# ProProject__CW32__2024-01-01.net
KiCad netlist of a schematic drawn in EasyEDA Pro
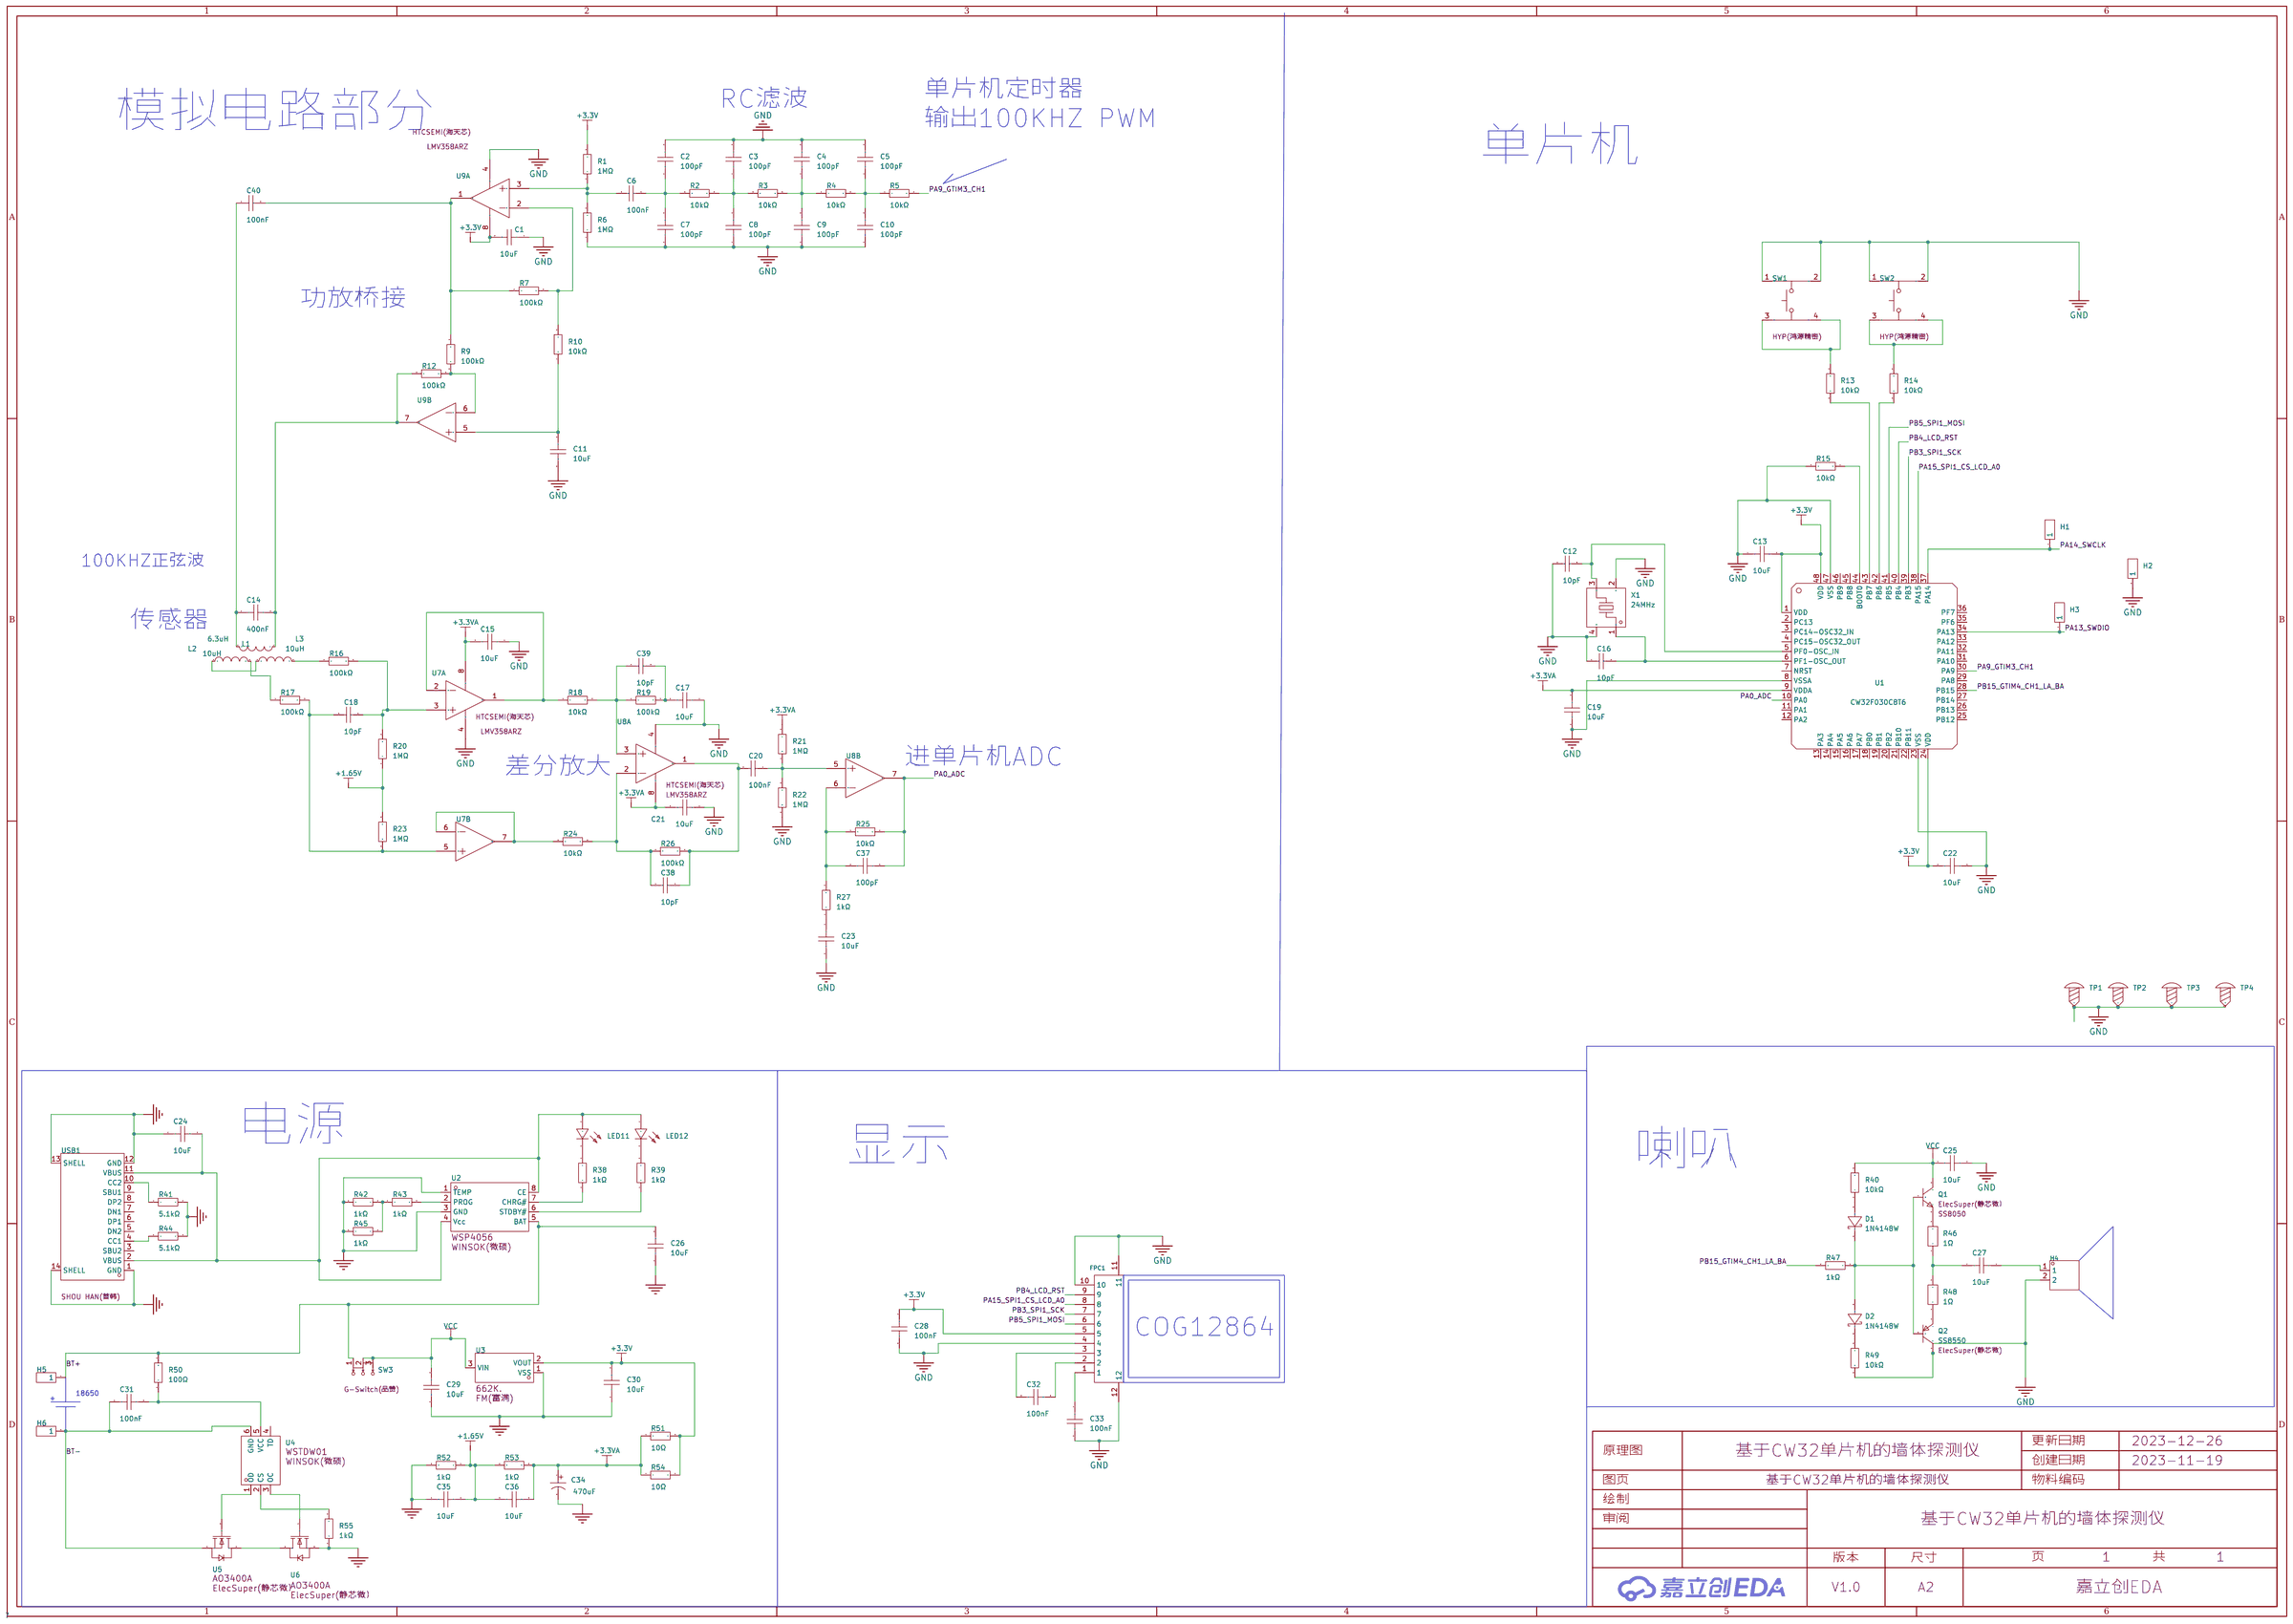
[diagram p0: schematic sheet]

(export (version "E")
  (design (tool "Eeschema 10.0.6"))
  (components
    (comp (ref "C1")
      (value "10uF")
      (footprint "easyedapro:C0603")
      (description "容值:10uF;精度:±10%;额定电压:10V;材质(温度系数):X5R;")
      (fields
        (field (name "Manufacturer Part") "CL10A106KP8NNNC")
        (field (name "Manufacturer") "SAMSUNG(三星)")
      )
      (libsource (lib "easyedapro") (part "CL10A106KP8NNNC"))
    )
    (comp (ref "C2")
      (value "100pF")
      (footprint "easyedapro:C0603")
      (description "容值:100pF;精度:±5%;额定电压:50V;材质(温度系数):NP0;")
      (fields
        (field (name "Manufacturer Part") "CC0603JRNPO9BN101")
        (field (name "Manufacturer") "YAGEO(国巨)")
      )
      (libsource (lib "easyedapro") (part "CC0603JRNPO9BN101"))
    )
    (comp (ref "C3")
      (value "100pF")
      (footprint "easyedapro:C0603")
      (description "容值:100pF;精度:±5%;额定电压:50V;材质(温度系数):NP0;")
      (fields
        (field (name "Manufacturer Part") "CC0603JRNPO9BN101")
        (field (name "Manufacturer") "YAGEO(国巨)")
      )
      (libsource (lib "easyedapro") (part "CC0603JRNPO9BN101"))
    )
    (comp (ref "C4")
      (value "100pF")
      (footprint "easyedapro:C0603")
      (description "容值:100pF;精度:±5%;额定电压:50V;材质(温度系数):NP0;")
      (fields
        (field (name "Manufacturer Part") "CC0603JRNPO9BN101")
        (field (name "Manufacturer") "YAGEO(国巨)")
      )
      (libsource (lib "easyedapro") (part "CC0603JRNPO9BN101"))
    )
    (comp (ref "C5")
      (value "100pF")
      (footprint "easyedapro:C0603")
      (description "容值:100pF;精度:±5%;额定电压:50V;材质(温度系数):NP0;")
      (fields
        (field (name "Manufacturer Part") "CC0603JRNPO9BN101")
        (field (name "Manufacturer") "YAGEO(国巨)")
      )
      (libsource (lib "easyedapro") (part "CC0603JRNPO9BN101"))
    )
    (comp (ref "C6")
      (value "100nF")
      (footprint "easyedapro:C0603")
      (description "容值:100nF;精度:±10%;额定电压:50V;材质(温度系数):X7R;")
      (fields (field (name "Manufacturer Part") "0603B104K500NT") (field (name "Manufacturer") "FH(风华)"))
      (libsource (lib "easyedapro") (part "0603B104K500NT"))
    )
    (comp (ref "C7")
      (value "100pF")
      (footprint "easyedapro:C0603")
      (description "容值:100pF;精度:±5%;额定电压:50V;材质(温度系数):NP0;")
      (fields
        (field (name "Manufacturer Part") "CC0603JRNPO9BN101")
        (field (name "Manufacturer") "YAGEO(国巨)")
      )
      (libsource (lib "easyedapro") (part "CC0603JRNPO9BN101"))
    )
    (comp (ref "C8")
      (value "100pF")
      (footprint "easyedapro:C0603")
      (description "容值:100pF;精度:±5%;额定电压:50V;材质(温度系数):NP0;")
      (fields
        (field (name "Manufacturer Part") "CC0603JRNPO9BN101")
        (field (name "Manufacturer") "YAGEO(国巨)")
      )
      (libsource (lib "easyedapro") (part "CC0603JRNPO9BN101"))
    )
    (comp (ref "C9")
      (value "100pF")
      (footprint "easyedapro:C0603")
      (description "容值:100pF;精度:±5%;额定电压:50V;材质(温度系数):NP0;")
      (fields
        (field (name "Manufacturer Part") "CC0603JRNPO9BN101")
        (field (name "Manufacturer") "YAGEO(国巨)")
      )
      (libsource (lib "easyedapro") (part "CC0603JRNPO9BN101"))
    )
    (comp (ref "C10")
      (value "100pF")
      (footprint "easyedapro:C0603")
      (description "容值:100pF;精度:±5%;额定电压:50V;材质(温度系数):NP0;")
      (fields
        (field (name "Manufacturer Part") "CC0603JRNPO9BN101")
        (field (name "Manufacturer") "YAGEO(国巨)")
      )
      (libsource (lib "easyedapro") (part "CC0603JRNPO9BN101"))
    )
    (comp (ref "C11")
      (value "10uF")
      (footprint "easyedapro:C0603")
      (description "容值:10uF;精度:±10%;额定电压:10V;材质(温度系数):X5R;")
      (fields
        (field (name "Manufacturer Part") "CL10A106KP8NNNC")
        (field (name "Manufacturer") "SAMSUNG(三星)")
      )
      (libsource (lib "easyedapro") (part "CL10A106KP8NNNC"))
    )
    (comp (ref "C12")
      (value "10pF")
      (footprint "easyedapro:C0603")
      (description "容值:10pF;精度:±5%;额定电压:50V;材质(温度系数):NP0;")
      (fields
        (field (name "Manufacturer Part") "CC0603JRNPO9BN100")
        (field (name "Manufacturer") "YAGEO(国巨)")
      )
      (libsource (lib "easyedapro") (part "CC0603JRNPO9BN100"))
    )
    (comp (ref "C13")
      (value "10uF")
      (footprint "easyedapro:C0603")
      (description "容值:10uF;精度:±10%;额定电压:10V;材质(温度系数):X5R;")
      (fields
        (field (name "Manufacturer Part") "CL10A106KP8NNNC")
        (field (name "Manufacturer") "SAMSUNG(三星)")
      )
      (libsource (lib "easyedapro") (part "CL10A106KP8NNNC"))
    )
    (comp (ref "C14")
      (value "400nF")
      (footprint "easyedapro:CAP-TH_L10.5-W6.0-P7.50-D1.2")
      (description "容值:400nF;精度:±5%;额定电压:100V;")
      (fields (field (name "Manufacturer Part") "MPP404J2A0701") (field (name "Manufacturer") "KYET(科雅)"))
      (libsource (lib "easyedapro") (part "MPP404J2A0701"))
    )
    (comp (ref "C15")
      (value "10uF")
      (footprint "easyedapro:C0603")
      (description "容值:10uF;精度:±10%;额定电压:10V;材质(温度系数):X5R;")
      (fields
        (field (name "Manufacturer Part") "CL10A106KP8NNNC")
        (field (name "Manufacturer") "SAMSUNG(三星)")
      )
      (libsource (lib "easyedapro") (part "CL10A106KP8NNNC"))
    )
    (comp (ref "C16")
      (value "10pF")
      (footprint "easyedapro:C0603")
      (description "容值:10pF;精度:±5%;额定电压:50V;材质(温度系数):NP0;")
      (fields
        (field (name "Manufacturer Part") "CC0603JRNPO9BN100")
        (field (name "Manufacturer") "YAGEO(国巨)")
      )
      (libsource (lib "easyedapro") (part "CC0603JRNPO9BN100"))
    )
    (comp (ref "C17")
      (value "10uF")
      (footprint "easyedapro:C0603")
      (description "容值:10uF;精度:±10%;额定电压:10V;材质(温度系数):X5R;")
      (fields
        (field (name "Manufacturer Part") "CL10A106KP8NNNC")
        (field (name "Manufacturer") "SAMSUNG(三星)")
      )
      (libsource (lib "easyedapro") (part "CL10A106KP8NNNC"))
    )
    (comp (ref "C18")
      (value "10pF")
      (footprint "easyedapro:C0603")
      (description "容值:10pF;精度:±5%;额定电压:50V;材质(温度系数):NP0;")
      (fields
        (field (name "Manufacturer Part") "CC0603JRNPO9BN100")
        (field (name "Manufacturer") "YAGEO(国巨)")
      )
      (libsource (lib "easyedapro") (part "CC0603JRNPO9BN100"))
    )
    (comp (ref "C19")
      (value "10uF")
      (footprint "easyedapro:C0603")
      (description "容值:10uF;精度:±10%;额定电压:10V;材质(温度系数):X5R;")
      (fields
        (field (name "Manufacturer Part") "CL10A106KP8NNNC")
        (field (name "Manufacturer") "SAMSUNG(三星)")
      )
      (libsource (lib "easyedapro") (part "CL10A106KP8NNNC"))
    )
    (comp (ref "C20")
      (value "100nF")
      (footprint "easyedapro:C0603")
      (description "容值:100nF;精度:±10%;额定电压:50V;材质(温度系数):X7R;")
      (fields (field (name "Manufacturer Part") "0603B104K500NT") (field (name "Manufacturer") "FH(风华)"))
      (libsource (lib "easyedapro") (part "0603B104K500NT"))
    )
    (comp (ref "C21")
      (value "10uF")
      (footprint "easyedapro:C0603")
      (description "容值:10uF;精度:±10%;额定电压:10V;材质(温度系数):X5R;")
      (fields
        (field (name "Manufacturer Part") "CL10A106KP8NNNC")
        (field (name "Manufacturer") "SAMSUNG(三星)")
      )
      (libsource (lib "easyedapro") (part "CL10A106KP8NNNC"))
    )
    (comp (ref "C22")
      (value "10uF")
      (footprint "easyedapro:C0603")
      (description "容值:10uF;精度:±10%;额定电压:10V;材质(温度系数):X5R;")
      (fields
        (field (name "Manufacturer Part") "CL10A106KP8NNNC")
        (field (name "Manufacturer") "SAMSUNG(三星)")
      )
      (libsource (lib "easyedapro") (part "CL10A106KP8NNNC"))
    )
    (comp (ref "C23")
      (value "10uF")
      (footprint "easyedapro:C0603")
      (description "容值:10uF;精度:±10%;额定电压:10V;材质(温度系数):X5R;")
      (fields
        (field (name "Manufacturer Part") "CL10A106KP8NNNC")
        (field (name "Manufacturer") "SAMSUNG(三星)")
      )
      (libsource (lib "easyedapro") (part "CL10A106KP8NNNC"))
    )
    (comp (ref "C24")
      (value "10uF")
      (footprint "easyedapro:C0603")
      (description "容值:10uF;精度:±10%;额定电压:10V;材质(温度系数):X5R;")
      (fields
        (field (name "Manufacturer Part") "CL10A106KP8NNNC")
        (field (name "Manufacturer") "SAMSUNG(三星)")
      )
      (libsource (lib "easyedapro") (part "CL10A106KP8NNNC"))
    )
    (comp (ref "C25")
      (value "10uF")
      (footprint "easyedapro:C0603")
      (description "容值:10uF;精度:±10%;额定电压:10V;材质(温度系数):X5R;")
      (fields
        (field (name "Manufacturer Part") "CL10A106KP8NNNC")
        (field (name "Manufacturer") "SAMSUNG(三星)")
      )
      (libsource (lib "easyedapro") (part "CL10A106KP8NNNC"))
    )
    (comp (ref "C26")
      (value "10uF")
      (footprint "easyedapro:C0603")
      (description "容值:10uF;精度:±10%;额定电压:10V;材质(温度系数):X5R;")
      (fields
        (field (name "Manufacturer Part") "CL10A106KP8NNNC")
        (field (name "Manufacturer") "SAMSUNG(三星)")
      )
      (libsource (lib "easyedapro") (part "CL10A106KP8NNNC"))
    )
    (comp (ref "C27")
      (value "10uF")
      (footprint "easyedapro:C0603")
      (description "容值:10uF;精度:±10%;额定电压:10V;材质(温度系数):X5R;")
      (fields
        (field (name "Manufacturer Part") "CL10A106KP8NNNC")
        (field (name "Manufacturer") "SAMSUNG(三星)")
      )
      (libsource (lib "easyedapro") (part "CL10A106KP8NNNC"))
    )
    (comp (ref "C28")
      (value "100nF")
      (footprint "easyedapro:C0603")
      (description "容值:100nF;精度:±10%;额定电压:50V;材质(温度系数):X7R;")
      (fields
        (field (name "Manufacturer Part") "CC0603KRX7R9BB104")
        (field (name "Manufacturer") "YAGEO(国巨)")
      )
      (libsource (lib "easyedapro") (part "CC0603KRX7R9BB104"))
    )
    (comp (ref "C29")
      (value "10uF")
      (footprint "easyedapro:C0603")
      (description "容值:10uF;精度:±10%;额定电压:10V;材质(温度系数):X5R;")
      (fields
        (field (name "Manufacturer Part") "CL10A106KP8NNNC")
        (field (name "Manufacturer") "SAMSUNG(三星)")
      )
      (libsource (lib "easyedapro") (part "CL10A106KP8NNNC"))
    )
    (comp (ref "C30")
      (value "10uF")
      (footprint "easyedapro:C0603")
      (description "容值:10uF;精度:±10%;额定电压:10V;材质(温度系数):X5R;")
      (fields
        (field (name "Manufacturer Part") "CL10A106KP8NNNC")
        (field (name "Manufacturer") "SAMSUNG(三星)")
      )
      (libsource (lib "easyedapro") (part "CL10A106KP8NNNC"))
    )
    (comp (ref "C31")
      (value "100nF")
      (footprint "easyedapro:C0603")
      (description "容值:100nF;精度:±10%;额定电压:50V;材质(温度系数):X7R;")
      (fields
        (field (name "Manufacturer Part") "CC0603KRX7R9BB104")
        (field (name "Manufacturer") "YAGEO(国巨)")
      )
      (libsource (lib "easyedapro") (part "CC0603KRX7R9BB104"))
    )
    (comp (ref "C32")
      (value "100nF")
      (footprint "easyedapro:C0603")
      (description "容值:100nF;精度:±10%;额定电压:50V;材质(温度系数):X7R;")
      (fields
        (field (name "Manufacturer Part") "CC0603KRX7R9BB104")
        (field (name "Manufacturer") "YAGEO(国巨)")
      )
      (libsource (lib "easyedapro") (part "CC0603KRX7R9BB104"))
    )
    (comp (ref "C33")
      (value "100nF")
      (footprint "easyedapro:C0603")
      (description "容值:100nF;精度:±10%;额定电压:50V;材质(温度系数):X7R;")
      (fields
        (field (name "Manufacturer Part") "CC0603KRX7R9BB104")
        (field (name "Manufacturer") "YAGEO(国巨)")
      )
      (libsource (lib "easyedapro") (part "CC0603KRX7R9BB104"))
    )
    (comp (ref "C34")
      (value "470uF")
      (footprint "easyedapro:CAP-TH_BD8.0-P3.50-D0.6-FD")
      (description "容值:470uF;精度:±20%;额定电压:16V;")
      (fields
        (field (name "Manufacturer Part") "KM477M016F12RR0VH2FP0")
        (field (name "Manufacturer") "CX(承兴)")
      )
      (libsource (lib "easyedapro") (part "470uf16v"))
    )
    (comp (ref "C35")
      (value "10uF")
      (footprint "easyedapro:C0603")
      (description "容值:10uF;精度:±10%;额定电压:10V;材质(温度系数):X5R;")
      (fields
        (field (name "Manufacturer Part") "CL10A106KP8NNNC")
        (field (name "Manufacturer") "SAMSUNG(三星)")
      )
      (libsource (lib "easyedapro") (part "CL10A106KP8NNNC"))
    )
    (comp (ref "C36")
      (value "10uF")
      (footprint "easyedapro:C0603")
      (description "容值:10uF;精度:±10%;额定电压:10V;材质(温度系数):X5R;")
      (fields
        (field (name "Manufacturer Part") "CL10A106KP8NNNC")
        (field (name "Manufacturer") "SAMSUNG(三星)")
      )
      (libsource (lib "easyedapro") (part "CL10A106KP8NNNC"))
    )
    (comp (ref "C37")
      (value "100pF")
      (footprint "easyedapro:C0603")
      (description "容值:100pF;精度:±5%;额定电压:50V;材质(温度系数):NP0;")
      (fields
        (field (name "Manufacturer Part") "CC0603JRNPO9BN101")
        (field (name "Manufacturer") "YAGEO(国巨)")
      )
      (libsource (lib "easyedapro") (part "CC0603JRNPO9BN101"))
    )
    (comp (ref "C38")
      (value "10pF")
      (footprint "easyedapro:C0603")
      (description "容值:10pF;精度:±5%;额定电压:50V;材质(温度系数):NP0;")
      (fields
        (field (name "Manufacturer Part") "CC0603JRNPO9BN100")
        (field (name "Manufacturer") "YAGEO(国巨)")
      )
      (libsource (lib "easyedapro") (part "CC0603JRNPO9BN100"))
    )
    (comp (ref "C39")
      (value "10pF")
      (footprint "easyedapro:C0603")
      (description "容值:10pF;精度:±5%;额定电压:50V;材质(温度系数):NP0;")
      (fields
        (field (name "Manufacturer Part") "CC0603JRNPO9BN100")
        (field (name "Manufacturer") "YAGEO(国巨)")
      )
      (libsource (lib "easyedapro") (part "CC0603JRNPO9BN100"))
    )
    (comp (ref "C40")
      (value "100nF")
      (footprint "easyedapro:C0603")
      (description "容值:100nF;精度:±10%;额定电压:50V;材质(温度系数):X7R;")
      (fields (field (name "Manufacturer Part") "0603B104K500NT") (field (name "Manufacturer") "FH(风华)"))
      (libsource (lib "easyedapro") (part "0603B104K500NT"))
    )
    (comp (ref "D1")
      (value "1N4148W")
      (footprint "easyedapro:SOD-123_L2.7-W1.6-LS3.7-FD")
      (description "二极管配置:独立式;正向压降(Vf):1.25V@150mA;直流反向耐压(Vr):100V;平均整流电流(Io):150mA;功率:400mW;反向恢复时间(trr):4ns;")
      (fields (field (name "Manufacturer") "宏迦橙"))
      (libsource (lib "easyedapro") (part "1N4148W_C7420318"))
    )
    (comp (ref "D2")
      (value "1N4148W")
      (footprint "easyedapro:SOD-123_L2.7-W1.6-LS3.7-FD")
      (description "二极管配置:独立式;正向压降(Vf):1.25V@150mA;直流反向耐压(Vr):100V;平均整流电流(Io):150mA;功率:400mW;反向恢复时间(trr):4ns;")
      (fields (field (name "Manufacturer") "宏迦橙"))
      (libsource (lib "easyedapro") (part "1N4148W_C7420318"))
    )
    (comp (ref "FPC1")
      (value "{ManufacturerPart!}")
      (footprint "easyedapro:FPC-SMD_10P-P1.0_FGS-XJ-H2.0")
      (description "间距:1mm;触点数量:10;锁定特性:翻盖式;安装类型:卧贴;触点类型:下接;")
      (fields (field (name "Manufacturer Part") "AFA01-S10FCA-00") (field (name "Manufacturer") "JS(钜硕电子)"))
      (libsource (lib "easyedapro") (part "AFA01-S10FCA-00"))
    )
    (comp (ref "H1")
      (value "~")
      (footprint "easyedapro:HDR-TH_1P-V-M_XKB_X4611WV-01I-C28D40")
      (libsource (lib "easyedapro") (part "HDR_1x1"))
    )
    (comp (ref "H2")
      (value "~")
      (footprint "easyedapro:HDR-TH_1P-V-M_XKB_X4611WV-01I-C28D40")
      (libsource (lib "easyedapro") (part "HDR_1x1"))
    )
    (comp (ref "H3")
      (value "~")
      (footprint "easyedapro:HDR-TH_1P-V-M_XKB_X4611WV-01I-C28D40")
      (libsource (lib "easyedapro") (part "HDR_1x1"))
    )
    (comp (ref "H4")
      (value "~")
      (footprint "easyedapro:HDR-TH_2P-P2.54-V-M-1")
      (libsource (lib "easyedapro") (part "210S-1*2P L=11.6MMGold-plated black"))
    )
    (comp (ref "H5")
      (value "~")
      (footprint "easyedapro:HDR-TH_1P-V-M_XKB_X4611WV-01I-C28D40")
      (libsource (lib "easyedapro") (part "HDR_1x1"))
    )
    (comp (ref "H6")
      (value "~")
      (footprint "easyedapro:HDR-TH_1P-V-M_XKB_X4611WV-01I-C28D40")
      (libsource (lib "easyedapro") (part "HDR_1x1"))
    )
    (comp (ref "L1")
      (value "6.3uH")
      (footprint "easyedapro:L1206")
      (libsource (lib "easyedapro") (part "CMI321609VR27KT"))
    )
    (comp (ref "L2")
      (value "10uH")
      (footprint "easyedapro:L1206")
      (libsource (lib "easyedapro") (part "CMI321609VR27KT"))
    )
    (comp (ref "L3")
      (value "10uH")
      (footprint "easyedapro:L1206")
      (libsource (lib "easyedapro") (part "CMI321609VR27KT"))
    )
    (comp (ref "LED11")
      (value "204-10SURD/S530-A3-L")
      (footprint "easyedapro:LED-TH_BD3.0-P2.54-FD")
      (description "发光颜色:红灯;二极管配置:-;主波长:624nm;色温:-;功率:60mW;安装方式:-;")
      (fields (field (name "Manufacturer") "EVERLIGHT(亿光)"))
      (libsource (lib "easyedapro") (part "204-10SURD/S530-A3-L"))
    )
    (comp (ref "LED12")
      (value "204-10SURD/S530-A3-L")
      (footprint "easyedapro:LED-TH_BD3.0-P2.54-FD")
      (description "发光颜色:红灯;二极管配置:-;主波长:624nm;色温:-;功率:60mW;安装方式:-;")
      (fields (field (name "Manufacturer") "EVERLIGHT(亿光)"))
      (libsource (lib "easyedapro") (part "204-10SURD/S530-A3-L"))
    )
    (comp (ref "Q1")
      (value "{ManufacturerPart!}")
      (footprint "easyedapro:SOT-23-3_L2.9-W1.3-P1.90-LS2.4-BR")
      (fields (field (name "Manufacturer Part") "SS8050") (field (name "Manufacturer") "ElecSuper(静芯微）"))
      (libsource (lib "easyedapro") (part "SS8050_C5249676"))
    )
    (comp (ref "Q2")
      (value "SS8550")
      (footprint "easyedapro:SOT-23-3_L2.9-W1.3-P1.90-LS2.4-BR")
      (description "晶体管类型:PNP;集电极电流(Ic):1.5A;集射极击穿电压(Vceo):25V;功率(Pd):300mW;直流电流增益(hFE@Ic,Vce):120;")
      (fields (field (name "Manufacturer") "ElecSuper(静芯微)"))
      (libsource (lib "easyedapro") (part "SS8550_C5249677"))
    )
    (comp (ref "R1")
      (value "1MΩ")
      (footprint "easyedapro:R0603")
      (description "电阻类型:厚膜电阻;阻值:1MΩ;精度:±1%;功率:100mW;")
      (fields
        (field (name "Manufacturer Part") "0603WAF1004T5E")
        (field (name "Manufacturer") "UNI-ROYAL(厚声)")
      )
      (libsource (lib "easyedapro") (part "0603WAF1004T5E"))
    )
    (comp (ref "R2")
      (value "10kΩ")
      (footprint "easyedapro:R0603")
      (description "电阻类型:厚膜电阻;阻值:10kΩ;精度:±1%;功率:100mW;")
      (fields (field (name "Manufacturer Part") "RC0603FR-0710KL") (field (name "Manufacturer") "YAGEO(国巨)"))
      (libsource (lib "easyedapro") (part "RC0603FR-0710KL"))
    )
    (comp (ref "R3")
      (value "10kΩ")
      (footprint "easyedapro:R0603")
      (description "电阻类型:厚膜电阻;阻值:10kΩ;精度:±1%;功率:100mW;")
      (fields (field (name "Manufacturer Part") "RC0603FR-0710KL") (field (name "Manufacturer") "YAGEO(国巨)"))
      (libsource (lib "easyedapro") (part "RC0603FR-0710KL"))
    )
    (comp (ref "R4")
      (value "10kΩ")
      (footprint "easyedapro:R0603")
      (description "电阻类型:厚膜电阻;阻值:10kΩ;精度:±1%;功率:100mW;")
      (fields (field (name "Manufacturer Part") "RC0603FR-0710KL") (field (name "Manufacturer") "YAGEO(国巨)"))
      (libsource (lib "easyedapro") (part "RC0603FR-0710KL"))
    )
    (comp (ref "R5")
      (value "10kΩ")
      (footprint "easyedapro:R0603")
      (description "电阻类型:厚膜电阻;阻值:10kΩ;精度:±1%;功率:100mW;")
      (fields (field (name "Manufacturer Part") "RC0603FR-0710KL") (field (name "Manufacturer") "YAGEO(国巨)"))
      (libsource (lib "easyedapro") (part "RC0603FR-0710KL"))
    )
    (comp (ref "R6")
      (value "1MΩ")
      (footprint "easyedapro:R0603")
      (description "电阻类型:厚膜电阻;阻值:1MΩ;精度:±1%;功率:100mW;")
      (fields
        (field (name "Manufacturer Part") "0603WAF1004T5E")
        (field (name "Manufacturer") "UNI-ROYAL(厚声)")
      )
      (libsource (lib "easyedapro") (part "0603WAF1004T5E"))
    )
    (comp (ref "R7")
      (value "100kΩ")
      (footprint "easyedapro:R0603")
      (description "电阻类型:厚膜电阻;阻值:100kΩ;精度:±1%;功率:100mW;")
      (fields (field (name "Manufacturer Part") "RC0603FR-07100KL") (field (name "Manufacturer") "YAGEO(国巨)"))
      (libsource (lib "easyedapro") (part "RC0603FR-07100KL"))
    )
    (comp (ref "R9")
      (value "100kΩ")
      (footprint "easyedapro:R0603")
      (description "电阻类型:厚膜电阻;阻值:100kΩ;精度:±1%;功率:100mW;")
      (fields (field (name "Manufacturer Part") "RC0603FR-07100KL") (field (name "Manufacturer") "YAGEO(国巨)"))
      (libsource (lib "easyedapro") (part "RC0603FR-07100KL"))
    )
    (comp (ref "R10")
      (value "10kΩ")
      (footprint "easyedapro:R0603")
      (description "电阻类型:厚膜电阻;阻值:10kΩ;精度:±1%;功率:100mW;")
      (fields (field (name "Manufacturer Part") "RC0603FR-0710KL") (field (name "Manufacturer") "YAGEO(国巨)"))
      (libsource (lib "easyedapro") (part "RC0603FR-0710KL"))
    )
    (comp (ref "R12")
      (value "100kΩ")
      (footprint "easyedapro:R0603")
      (description "电阻类型:厚膜电阻;阻值:100kΩ;精度:±1%;功率:100mW;")
      (fields (field (name "Manufacturer Part") "RC0603FR-07100KL") (field (name "Manufacturer") "YAGEO(国巨)"))
      (libsource (lib "easyedapro") (part "RC0603FR-07100KL"))
    )
    (comp (ref "R13")
      (value "10kΩ")
      (footprint "easyedapro:R0603")
      (description "电阻类型:厚膜电阻;阻值:10kΩ;精度:±1%;功率:100mW;")
      (fields (field (name "Manufacturer Part") "RC0603FR-0710KL") (field (name "Manufacturer") "YAGEO(国巨)"))
      (libsource (lib "easyedapro") (part "RC0603FR-0710KL"))
    )
    (comp (ref "R14")
      (value "10kΩ")
      (footprint "easyedapro:R0603")
      (description "电阻类型:厚膜电阻;阻值:10kΩ;精度:±1%;功率:100mW;")
      (fields (field (name "Manufacturer Part") "RC0603FR-0710KL") (field (name "Manufacturer") "YAGEO(国巨)"))
      (libsource (lib "easyedapro") (part "RC0603FR-0710KL"))
    )
    (comp (ref "R15")
      (value "10kΩ")
      (footprint "easyedapro:R0603")
      (description "电阻类型:厚膜电阻;阻值:10kΩ;精度:±1%;功率:100mW;")
      (fields (field (name "Manufacturer Part") "RC0603FR-0710KL") (field (name "Manufacturer") "YAGEO(国巨)"))
      (libsource (lib "easyedapro") (part "RC0603FR-0710KL"))
    )
    (comp (ref "R16")
      (value "100kΩ")
      (footprint "easyedapro:R0603")
      (description "电阻类型:厚膜电阻;阻值:100kΩ;精度:±1%;功率:100mW;")
      (fields (field (name "Manufacturer Part") "RC0603FR-07100KL") (field (name "Manufacturer") "YAGEO(国巨)"))
      (libsource (lib "easyedapro") (part "RC0603FR-07100KL"))
    )
    (comp (ref "R17")
      (value "100kΩ")
      (footprint "easyedapro:R0603")
      (description "电阻类型:厚膜电阻;阻值:100kΩ;精度:±1%;功率:100mW;")
      (fields (field (name "Manufacturer Part") "RC0603FR-07100KL") (field (name "Manufacturer") "YAGEO(国巨)"))
      (libsource (lib "easyedapro") (part "RC0603FR-07100KL"))
    )
    (comp (ref "R18")
      (value "10kΩ")
      (footprint "easyedapro:R0603")
      (description "电阻类型:厚膜电阻;阻值:10kΩ;精度:±1%;功率:100mW;")
      (fields (field (name "Manufacturer Part") "RC0603FR-0710KL") (field (name "Manufacturer") "YAGEO(国巨)"))
      (libsource (lib "easyedapro") (part "RC0603FR-0710KL"))
    )
    (comp (ref "R19")
      (value "100kΩ")
      (footprint "easyedapro:R0603")
      (description "电阻类型:厚膜电阻;阻值:100kΩ;精度:±1%;功率:100mW;")
      (fields (field (name "Manufacturer Part") "RC0603FR-07100KL") (field (name "Manufacturer") "YAGEO(国巨)"))
      (libsource (lib "easyedapro") (part "RC0603FR-07100KL"))
    )
    (comp (ref "R20")
      (value "1MΩ")
      (footprint "easyedapro:R0603")
      (description "电阻类型:厚膜电阻;阻值:1MΩ;精度:±1%;功率:100mW;")
      (fields
        (field (name "Manufacturer Part") "0603WAF1004T5E")
        (field (name "Manufacturer") "UNI-ROYAL(厚声)")
      )
      (libsource (lib "easyedapro") (part "0603WAF1004T5E"))
    )
    (comp (ref "R21")
      (value "1MΩ")
      (footprint "easyedapro:R0603")
      (description "电阻类型:厚膜电阻;阻值:1MΩ;精度:±1%;功率:100mW;")
      (fields
        (field (name "Manufacturer Part") "0603WAF1004T5E")
        (field (name "Manufacturer") "UNI-ROYAL(厚声)")
      )
      (libsource (lib "easyedapro") (part "0603WAF1004T5E"))
    )
    (comp (ref "R22")
      (value "1MΩ")
      (footprint "easyedapro:R0603")
      (description "电阻类型:厚膜电阻;阻值:1MΩ;精度:±1%;功率:100mW;")
      (fields
        (field (name "Manufacturer Part") "0603WAF1004T5E")
        (field (name "Manufacturer") "UNI-ROYAL(厚声)")
      )
      (libsource (lib "easyedapro") (part "0603WAF1004T5E"))
    )
    (comp (ref "R23")
      (value "1MΩ")
      (footprint "easyedapro:R0603")
      (description "电阻类型:厚膜电阻;阻值:1MΩ;精度:±1%;功率:100mW;")
      (fields
        (field (name "Manufacturer Part") "0603WAF1004T5E")
        (field (name "Manufacturer") "UNI-ROYAL(厚声)")
      )
      (libsource (lib "easyedapro") (part "0603WAF1004T5E"))
    )
    (comp (ref "R24")
      (value "10kΩ")
      (footprint "easyedapro:R0603")
      (description "电阻类型:厚膜电阻;阻值:10kΩ;精度:±1%;功率:100mW;")
      (fields (field (name "Manufacturer Part") "RC0603FR-0710KL") (field (name "Manufacturer") "YAGEO(国巨)"))
      (libsource (lib "easyedapro") (part "RC0603FR-0710KL"))
    )
    (comp (ref "R25")
      (value "10kΩ")
      (footprint "easyedapro:R0603")
      (description "电阻类型:厚膜电阻;阻值:10kΩ;精度:±1%;功率:100mW;")
      (fields (field (name "Manufacturer Part") "RC0603FR-0710KL") (field (name "Manufacturer") "YAGEO(国巨)"))
      (libsource (lib "easyedapro") (part "RC0603FR-0710KL"))
    )
    (comp (ref "R26")
      (value "100kΩ")
      (footprint "easyedapro:R0603")
      (description "电阻类型:厚膜电阻;阻值:100kΩ;精度:±1%;功率:100mW;")
      (fields (field (name "Manufacturer Part") "RC0603FR-07100KL") (field (name "Manufacturer") "YAGEO(国巨)"))
      (libsource (lib "easyedapro") (part "RC0603FR-07100KL"))
    )
    (comp (ref "R27")
      (value "1kΩ")
      (footprint "easyedapro:R0603")
      (description "电阻类型:厚膜电阻;阻值:1kΩ;精度:±1%;功率:100mW;")
      (fields (field (name "Manufacturer Part") "RC0603FR-071KL") (field (name "Manufacturer") "YAGEO(国巨)"))
      (libsource (lib "easyedapro") (part "RC0603FR-071KL"))
    )
    (comp (ref "R38")
      (value "1kΩ")
      (footprint "easyedapro:R0603")
      (description "电阻类型:厚膜电阻;阻值:1kΩ;精度:±1%;功率:100mW;")
      (fields (field (name "Manufacturer Part") "RC0603FR-071KL") (field (name "Manufacturer") "YAGEO(国巨)"))
      (libsource (lib "easyedapro") (part "RC0603FR-071KL"))
    )
    (comp (ref "R39")
      (value "1kΩ")
      (footprint "easyedapro:R0603")
      (description "电阻类型:厚膜电阻;阻值:1kΩ;精度:±1%;功率:100mW;")
      (fields (field (name "Manufacturer Part") "RC0603FR-071KL") (field (name "Manufacturer") "YAGEO(国巨)"))
      (libsource (lib "easyedapro") (part "RC0603FR-071KL"))
    )
    (comp (ref "R40")
      (value "10kΩ")
      (footprint "easyedapro:R0603")
      (description "电阻类型:厚膜电阻;阻值:10kΩ;精度:±1%;功率:100mW;")
      (fields (field (name "Manufacturer Part") "RC0603FR-0710KL") (field (name "Manufacturer") "YAGEO(国巨)"))
      (libsource (lib "easyedapro") (part "RC0603FR-0710KL"))
    )
    (comp (ref "R41")
      (value "5.1kΩ")
      (footprint "easyedapro:R0603")
      (description "电阻类型:厚膜电阻;阻值:10kΩ;精度:±1%;功率:100mW;")
      (fields (field (name "Manufacturer Part") "RC0603FR-0710KL") (field (name "Manufacturer") "YAGEO(国巨)"))
      (libsource (lib "easyedapro") (part "RC0603FR-0710KL"))
    )
    (comp (ref "R42")
      (value "1kΩ")
      (footprint "easyedapro:R0603")
      (description "电阻类型:厚膜电阻;阻值:1kΩ;精度:±1%;功率:100mW;")
      (fields (field (name "Manufacturer Part") "RC0603FR-071KL") (field (name "Manufacturer") "YAGEO(国巨)"))
      (libsource (lib "easyedapro") (part "RC0603FR-071KL"))
    )
    (comp (ref "R43")
      (value "1kΩ")
      (footprint "easyedapro:R0603")
      (description "电阻类型:厚膜电阻;阻值:1kΩ;精度:±1%;功率:100mW;")
      (fields (field (name "Manufacturer Part") "RC0603FR-071KL") (field (name "Manufacturer") "YAGEO(国巨)"))
      (libsource (lib "easyedapro") (part "RC0603FR-071KL"))
    )
    (comp (ref "R44")
      (value "5.1kΩ")
      (footprint "easyedapro:R0603")
      (description "电阻类型:厚膜电阻;阻值:10kΩ;精度:±1%;功率:100mW;")
      (fields (field (name "Manufacturer Part") "RC0603FR-0710KL") (field (name "Manufacturer") "YAGEO(国巨)"))
      (libsource (lib "easyedapro") (part "RC0603FR-0710KL"))
    )
    (comp (ref "R45")
      (value "1kΩ")
      (footprint "easyedapro:R0603")
      (description "电阻类型:厚膜电阻;阻值:1kΩ;精度:±1%;功率:100mW;")
      (fields (field (name "Manufacturer Part") "RC0603FR-071KL") (field (name "Manufacturer") "YAGEO(国巨)"))
      (libsource (lib "easyedapro") (part "RC0603FR-071KL"))
    )
    (comp (ref "R46")
      (value "1Ω")
      (footprint "easyedapro:R0603")
      (description "阻值:1Ω;精度:±1%;")
      (fields (field (name "Manufacturer Part") "SCR0603F1R") (field (name "Manufacturer") "VO(翔胜)"))
      (libsource (lib "easyedapro") (part "SCR0603F1R"))
    )
    (comp (ref "R47")
      (value "1kΩ")
      (footprint "easyedapro:R0603")
      (description "电阻类型:厚膜电阻;阻值:1kΩ;精度:±1%;功率:100mW;")
      (fields (field (name "Manufacturer Part") "RC0603FR-071KL") (field (name "Manufacturer") "YAGEO(国巨)"))
      (libsource (lib "easyedapro") (part "RC0603FR-071KL"))
    )
    (comp (ref "R48")
      (value "1Ω")
      (footprint "easyedapro:R0603")
      (description "阻值:1Ω;精度:±1%;")
      (fields (field (name "Manufacturer Part") "SCR0603F1R") (field (name "Manufacturer") "VO(翔胜)"))
      (libsource (lib "easyedapro") (part "SCR0603F1R"))
    )
    (comp (ref "R49")
      (value "10kΩ")
      (footprint "easyedapro:R0603")
      (description "电阻类型:厚膜电阻;阻值:10kΩ;精度:±1%;功率:100mW;")
      (fields (field (name "Manufacturer Part") "RC0603FR-0710KL") (field (name "Manufacturer") "YAGEO(国巨)"))
      (libsource (lib "easyedapro") (part "RC0603FR-0710KL"))
    )
    (comp (ref "R50")
      (value "100Ω")
      (footprint "easyedapro:R0603")
      (description "电阻类型:厚膜电阻;阻值:100Ω;精度:±1%;功率:100mW;")
      (fields (field (name "Manufacturer Part") "RC0603FR-07100RL") (field (name "Manufacturer") "YAGEO(国巨)"))
      (libsource (lib "easyedapro") (part "RC0603FR-07100RL"))
    )
    (comp (ref "R51")
      (value "10Ω")
      (footprint "easyedapro:R0603")
      (description "电阻类型:厚膜电阻;阻值:10Ω;精度:±1%;功率:100mW;")
      (fields
        (field (name "Manufacturer Part") "0603WAF100JT5E")
        (field (name "Manufacturer") "UNI-ROYAL(厚声)")
      )
      (libsource (lib "easyedapro") (part "0603WAF100JT5E"))
    )
    (comp (ref "R52")
      (value "1kΩ")
      (footprint "easyedapro:R0603")
      (description "电阻类型:厚膜电阻;阻值:1kΩ;精度:±1%;功率:100mW;")
      (fields (field (name "Manufacturer Part") "RC0603FR-071KL") (field (name "Manufacturer") "YAGEO(国巨)"))
      (libsource (lib "easyedapro") (part "RC0603FR-071KL"))
    )
    (comp (ref "R53")
      (value "1kΩ")
      (footprint "easyedapro:R0603")
      (description "电阻类型:厚膜电阻;阻值:1kΩ;精度:±1%;功率:100mW;")
      (fields (field (name "Manufacturer Part") "RC0603FR-071KL") (field (name "Manufacturer") "YAGEO(国巨)"))
      (libsource (lib "easyedapro") (part "RC0603FR-071KL"))
    )
    (comp (ref "R54")
      (value "10Ω")
      (footprint "easyedapro:R0603")
      (description "电阻类型:厚膜电阻;阻值:10Ω;精度:±1%;功率:100mW;")
      (fields
        (field (name "Manufacturer Part") "0603WAF100JT5E")
        (field (name "Manufacturer") "UNI-ROYAL(厚声)")
      )
      (libsource (lib "easyedapro") (part "0603WAF100JT5E"))
    )
    (comp (ref "R55")
      (value "1kΩ")
      (footprint "easyedapro:R0603")
      (description "电阻类型:厚膜电阻;阻值:1kΩ;精度:±1%;功率:100mW;")
      (fields (field (name "Manufacturer Part") "RC0603FR-071KL") (field (name "Manufacturer") "YAGEO(国巨)"))
      (libsource (lib "easyedapro") (part "RC0603FR-071KL"))
    )
    (comp (ref "SW1")
      (value "{ManufacturerPart!}")
      (footprint "easyedapro:SW-TH_4P-L6.0-W6.0-P3.90-LS6.5")
      (description "触点电流:50mA;额定电压(DC):12V;额定功率:0.6W;绝缘电阻:100MΩ;电路结构:单刀单掷;安装方式:直插;带灯:无;作用力:250gf@±50gf;机械寿命:7万次;带支架:否;")
      (fields
        (field (name "Manufacturer Part") "1TS005A-2500-5001")
        (field (name "Manufacturer") "HYP(鸿源精密)")
      )
      (libsource (lib "easyedapro") (part "1TS005A-2500-5001"))
    )
    (comp (ref "SW2")
      (value "{ManufacturerPart!}")
      (footprint "easyedapro:SW-TH_4P-L6.0-W6.0-P3.90-LS6.5")
      (description "触点电流:50mA;额定电压(DC):12V;额定功率:0.6W;绝缘电阻:100MΩ;电路结构:单刀单掷;安装方式:直插;带灯:无;作用力:250gf@±50gf;机械寿命:7万次;带支架:否;")
      (fields
        (field (name "Manufacturer Part") "1TS005A-2500-5001")
        (field (name "Manufacturer") "HYP(鸿源精密)")
      )
      (libsource (lib "easyedapro") (part "1TS005A-2500-5001"))
    )
    (comp (ref "SW3")
      (value "SS-12F20-G070")
      (footprint "easyedapro:SW-TH_G-SWITCH_SS-12F20-G070")
      (description "额定电流(DC):500mA;额定电压(DC):250V;电路结构:单刀双掷;安装方式:直插;机械寿命:-;开关颜色:黑色;")
      (fields (field (name "Manufacturer") "G-Switch(品赞)"))
      (libsource (lib "easyedapro") (part "SS-12F20-G070"))
    )
    (comp (ref "TP1") (value "~") (footprint "easyedapro:M3螺丝") (libsource (lib "easyedapro") (part "螺丝孔")))
    (comp (ref "TP2") (value "~") (footprint "easyedapro:M3螺丝") (libsource (lib "easyedapro") (part "螺丝孔")))
    (comp (ref "TP3") (value "~") (footprint "easyedapro:M3螺丝") (libsource (lib "easyedapro") (part "螺丝孔")))
    (comp (ref "TP4") (value "~") (footprint "easyedapro:M3螺丝") (libsource (lib "easyedapro") (part "螺丝孔")))
    (comp (ref "U1")
      (value "CW32F030C8T6")
      (footprint "easyedapro:LQFP-48_L7.0-W7.0-P0.50-LS9.0-TL")
      (fields (field (name "Manufacturer") "CW(芯源)"))
      (libsource (lib "easyedapro") (part "CW32F030C8T6_C3019113"))
    )
    (comp (ref "U2")
      (value "WSP4056")
      (footprint "easyedapro:SOP-8_L5.1-W3.9-P1.27-LS6.0-BL")
      (fields (field (name "Manufacturer Part") "WSP4056") (field (name "Manufacturer") "WINSOK(微硕)"))
      (libsource (lib "easyedapro") (part "WSP4056"))
    )
    (comp (ref "U3")
      (value "662K.")
      (footprint "easyedapro:SOT-23-3_L2.9-W1.3-P1.90-LS2.4-BR")
      (description "输出类型:-;")
      (fields (field (name "Manufacturer Part") "662K.") (field (name "Manufacturer") "FM(富满)"))
      (libsource (lib "easyedapro") (part "662K."))
    )
    (comp (ref "U4")
      (value "WSTDW01")
      (footprint "easyedapro:SOT-23-6_L2.9-W1.6-P0.95-LS2.8-BR")
      (description "充电电池的类型:-;电池单元组数:-;最大充电电流:-;充满的电池组电压:-;最大供应电压:-;")
      (fields (field (name "Manufacturer Part") "WSTDW01") (field (name "Manufacturer") "WINSOK(微硕)"))
      (libsource (lib "easyedapro") (part "WSTDW01"))
    )
    (comp (ref "U5")
      (value "AO3400A")
      (footprint "easyedapro:SOT-23-3_L3.0-W1.6-P1.90-LS2.8-BR")
      (description "类型:N沟道;漏源电压(Vdss):30V;连续漏极电流(Id):6A;功率(Pd):1.4W;导通电阻(RDS(on)@Vgs,Id):19mΩ@10V,6.0A;")
      (fields (field (name "Manufacturer Part") "AO3400A") (field (name "Manufacturer") "ElecSuper(静芯微）"))
      (libsource (lib "easyedapro") (part "AO3400A_C5224194"))
    )
    (comp (ref "U6")
      (value "AO3400A")
      (footprint "easyedapro:SOT-23-3_L3.0-W1.6-P1.90-LS2.8-BR")
      (description "类型:N沟道;漏源电压(Vdss):30V;连续漏极电流(Id):6A;功率(Pd):1.4W;导通电阻(RDS(on)@Vgs,Id):19mΩ@10V,6.0A;")
      (fields (field (name "Manufacturer Part") "AO3400A") (field (name "Manufacturer") "ElecSuper(静芯微）"))
      (libsource (lib "easyedapro") (part "AO3400A_C5224194"))
    )
    (comp (ref "U7")
      (value "{ManufacturerPart!}")
      (footprint "easyedapro:SOP-8_L4.9-W3.9-P1.27-LS6.0-BL")
      (description "CMOS低功耗双路运算放大器")
      (fields (field (name "Manufacturer Part") "LMV358ARZ") (field (name "Manufacturer") "HTCSEMI(海天芯)"))
      (libsource (lib "easyedapro") (part "LMV358ARZ"))
    )
    (comp (ref "U8")
      (value "{ManufacturerPart!}")
      (footprint "easyedapro:SOP-8_L4.9-W3.9-P1.27-LS6.0-BL")
      (description "CMOS低功耗双路运算放大器")
      (fields (field (name "Manufacturer Part") "LMV358ARZ") (field (name "Manufacturer") "HTCSEMI(海天芯)"))
      (libsource (lib "easyedapro") (part "LMV358ARZ"))
    )
    (comp (ref "U9")
      (value "{ManufacturerPart!}")
      (footprint "easyedapro:SOP-8_L4.9-W3.9-P1.27-LS6.0-BL")
      (description "CMOS低功耗双路运算放大器")
      (fields (field (name "Manufacturer Part") "LMV358ARZ") (field (name "Manufacturer") "HTCSEMI(海天芯)"))
      (libsource (lib "easyedapro") (part "LMV358ARZ"))
    )
    (comp (ref "USB1")
      (value "TYPE-C16PIN2MD(073)")
      (footprint "easyedapro:USB-C-SMD_TYPE-C-6PIN-2MD-073")
      (description "连接器类型:Type-C;标准:-;公母:母座;触点数量:16;端口数量:1;安装方式:卧贴;额定电流 - 电源:5A;工作温度范围:-25°C~+85°C;")
      (fields (field (name "Manufacturer") "SHOU HAN(首韩)"))
      (libsource (lib "easyedapro") (part "TYPE-C 16PIN 2MD(073)"))
    )
    (comp (ref "X1")
      (value "24MHz")
      (footprint "easyedapro:CRYSTAL-SMD_4P-L3.2-W2.5-BL")
      (description "频率:24MHz;频率公差:±10ppm;负载电容:9pF;")
      (fields (field (name "Manufacturer Part") "3TJ424000HYFBC") (field (name "Manufacturer") "JYJE(晶友嘉)"))
      (libsource (lib "easyedapro") (part "3TJ424000HYFBC"))
    )
  )
  (nets
    (net (code "1") (name "+1.65V") (class "Default")
      (node (ref "C35") (pin "2") (pinfunction "2_2") (pintype "unspecified"))
      (node (ref "C36") (pin "1") (pinfunction "1_1") (pintype "unspecified"))
      (node (ref "R20") (pin "1") (pinfunction "1_1") (pintype "input"))
      (node (ref "R23") (pin "2") (pinfunction "2_2") (pintype "input"))
      (node (ref "R52") (pin "1") (pinfunction "1_1") (pintype "input"))
      (node (ref "R53") (pin "2") (pinfunction "2_2") (pintype "input"))
    )
    (net (code "2") (name "+3.3V") (class "Default")
      (node (ref "C1") (pin "2") (pinfunction "2_2") (pintype "unspecified"))
      (node (ref "C13") (pin "2") (pinfunction "2_2") (pintype "unspecified"))
      (node (ref "C22") (pin "1") (pinfunction "1_1") (pintype "unspecified"))
      (node (ref "C28") (pin "1") (pinfunction "1_1") (pintype "unspecified"))
      (node (ref "C30") (pin "2") (pinfunction "2_2") (pintype "unspecified"))
      (node (ref "FPC1") (pin "5") (pinfunction "5_5") (pintype "input"))
      (node (ref "R1") (pin "2") (pinfunction "2_2") (pintype "input"))
      (node (ref "R51") (pin "2") (pinfunction "2_2") (pintype "input"))
      (node (ref "R54") (pin "2") (pinfunction "2_2") (pintype "input"))
      (node (ref "U1") (pin "1") (pinfunction "VDD_1") (pintype "input"))
      (node (ref "U1") (pin "24") (pinfunction "VDD_24") (pintype "input"))
      (node (ref "U1") (pin "48") (pinfunction "VDD_48") (pintype "input"))
      (node (ref "U3") (pin "2") (pinfunction "VOUT_2") (pintype "input"))
      (node (ref "U9") (pin "8") (pinfunction "VCC_8") (pintype "input"))
    )
    (net (code "3") (name "+3.3VA") (class "Default")
      (node (ref "C15") (pin "2") (pinfunction "2_2") (pintype "unspecified"))
      (node (ref "C19") (pin "2") (pinfunction "2_2") (pintype "unspecified"))
      (node (ref "C21") (pin "2") (pinfunction "2_2") (pintype "unspecified"))
      (node (ref "C34") (pin "1") (pinfunction "1_1") (pintype "input"))
      (node (ref "C36") (pin "2") (pinfunction "2_2") (pintype "unspecified"))
      (node (ref "R21") (pin "2") (pinfunction "2_2") (pintype "input"))
      (node (ref "R51") (pin "1") (pinfunction "1_1") (pintype "input"))
      (node (ref "R53") (pin "1") (pinfunction "1_1") (pintype "input"))
      (node (ref "R54") (pin "1") (pinfunction "1_1") (pintype "input"))
      (node (ref "U1") (pin "9") (pinfunction "VDDA_9") (pintype "input"))
      (node (ref "U7") (pin "8") (pinfunction "VCC_8") (pintype "input"))
      (node (ref "U8") (pin "8") (pinfunction "VCC_8") (pintype "input"))
    )
    (net (code "4") (name "/BT+") (class "Default")
      (node (ref "C26") (pin "2") (pinfunction "2_2") (pintype "unspecified"))
      (node (ref "H5") (pin "1") (pinfunction "1_1") (pintype "unspecified"))
      (node (ref "R50") (pin "2") (pinfunction "2_2") (pintype "input"))
      (node (ref "SW3") (pin "1") (pinfunction "1_1") (pintype "input"))
      (node (ref "U2") (pin "5") (pinfunction "BAT_5") (pintype "input"))
    )
    (net (code "5") (name "/BT-") (class "Default")
      (node (ref "C31") (pin "1") (pinfunction "1_1") (pintype "unspecified"))
      (node (ref "H6") (pin "1") (pinfunction "1_1") (pintype "unspecified"))
      (node (ref "U4") (pin "6") (pinfunction "GND_6") (pintype "input"))
      (node (ref "U5") (pin "2") (pinfunction "S_2") (pintype "input"))
    )
    (net (code "6") (name "/PA0_ADC") (class "Default")
      (node (ref "C37") (pin "1") (pinfunction "1_1") (pintype "unspecified"))
      (node (ref "R25") (pin "2") (pinfunction "2_2") (pintype "input"))
      (node (ref "U1") (pin "10") (pinfunction "PA0_10") (pintype "input"))
      (node (ref "U8") (pin "7") (pinfunction "OUT2_7") (pintype "output"))
    )
    (net (code "7") (name "/PA9_GTIM3_CH1") (class "Default")
      (node (ref "R5") (pin "2") (pinfunction "2_2") (pintype "input"))
      (node (ref "U1") (pin "30") (pinfunction "PA9_30") (pintype "input"))
    )
    (net (code "8") (name "/PA13_SWDIO") (class "Default")
      (node (ref "H3") (pin "1") (pinfunction "1_1") (pintype "unspecified"))
      (node (ref "U1") (pin "34") (pinfunction "PA13_34") (pintype "input"))
    )
    (net (code "9") (name "/PA14_SWCLK") (class "Default")
      (node (ref "H1") (pin "1") (pinfunction "1_1") (pintype "unspecified"))
      (node (ref "U1") (pin "37") (pinfunction "PA14_37") (pintype "input"))
    )
    (net (code "10") (name "/PA15_SPI1_CS_LCD_A0") (class "Default")
      (node (ref "FPC1") (pin "8") (pinfunction "8_8") (pintype "input"))
      (node (ref "U1") (pin "38") (pinfunction "PA15_38") (pintype "input"))
    )
    (net (code "11") (name "/PB3_SPI1_SCK") (class "Default")
      (node (ref "FPC1") (pin "7") (pinfunction "7_7") (pintype "input"))
      (node (ref "U1") (pin "39") (pinfunction "PB3_39") (pintype "input"))
    )
    (net (code "12") (name "/PB4_LCD_RST") (class "Default")
      (node (ref "FPC1") (pin "9") (pinfunction "9_9") (pintype "input"))
      (node (ref "U1") (pin "40") (pinfunction "PB4_40") (pintype "input"))
    )
    (net (code "13") (name "/PB5_SPI1_MOSI") (class "Default")
      (node (ref "FPC1") (pin "6") (pinfunction "6_6") (pintype "input"))
      (node (ref "U1") (pin "41") (pinfunction "PB5_41") (pintype "input"))
    )
    (net (code "14") (name "/PB15_GTIM4_CH1_LA_BA") (class "Default")
      (node (ref "R47") (pin "2") (pinfunction "2_2") (pintype "input"))
      (node (ref "U1") (pin "28") (pinfunction "PB15_28") (pintype "input"))
    )
    (net (code "15") (name "GND") (class "Default")
      (node (ref "C1") (pin "1") (pinfunction "1_1") (pintype "unspecified"))
      (node (ref "C10") (pin "1") (pinfunction "1_1") (pintype "unspecified"))
      (node (ref "C11") (pin "2") (pinfunction "2_2") (pintype "unspecified"))
      (node (ref "C12") (pin "1") (pinfunction "1_1") (pintype "input"))
      (node (ref "C13") (pin "1") (pinfunction "1_1") (pintype "unspecified"))
      (node (ref "C15") (pin "1") (pinfunction "1_1") (pintype "unspecified"))
      (node (ref "C16") (pin "1") (pinfunction "1_1") (pintype "input"))
      (node (ref "C17") (pin "1") (pinfunction "1_1") (pintype "unspecified"))
      (node (ref "C19") (pin "1") (pinfunction "1_1") (pintype "unspecified"))
      (node (ref "C2") (pin "2") (pinfunction "2_2") (pintype "unspecified"))
      (node (ref "C21") (pin "1") (pinfunction "1_1") (pintype "unspecified"))
      (node (ref "C22") (pin "2") (pinfunction "2_2") (pintype "unspecified"))
      (node (ref "C23") (pin "2") (pinfunction "2_2") (pintype "unspecified"))
      (node (ref "C24") (pin "1") (pinfunction "1_1") (pintype "unspecified"))
      (node (ref "C25") (pin "2") (pinfunction "2_2") (pintype "unspecified"))
      (node (ref "C26") (pin "1") (pinfunction "1_1") (pintype "unspecified"))
      (node (ref "C28") (pin "2") (pinfunction "2_2") (pintype "unspecified"))
      (node (ref "C29") (pin "1") (pinfunction "1_1") (pintype "unspecified"))
      (node (ref "C3") (pin "2") (pinfunction "2_2") (pintype "unspecified"))
      (node (ref "C30") (pin "1") (pinfunction "1_1") (pintype "unspecified"))
      (node (ref "C33") (pin "2") (pinfunction "2_2") (pintype "unspecified"))
      (node (ref "C34") (pin "2") (pinfunction "2_2") (pintype "input"))
      (node (ref "C35") (pin "1") (pinfunction "1_1") (pintype "unspecified"))
      (node (ref "C4") (pin "2") (pinfunction "2_2") (pintype "unspecified"))
      (node (ref "C5") (pin "2") (pinfunction "2_2") (pintype "unspecified"))
      (node (ref "C7") (pin "1") (pinfunction "1_1") (pintype "unspecified"))
      (node (ref "C8") (pin "1") (pinfunction "1_1") (pintype "unspecified"))
      (node (ref "C9") (pin "1") (pinfunction "1_1") (pintype "unspecified"))
      (node (ref "FPC1") (pin "10") (pinfunction "10_10") (pintype "input"))
      (node (ref "FPC1") (pin "11") (pinfunction "11_11") (pintype "input"))
      (node (ref "FPC1") (pin "12") (pinfunction "12_12") (pintype "input"))
      (node (ref "FPC1") (pin "4") (pinfunction "4_4") (pintype "input"))
      (node (ref "H2") (pin "1") (pinfunction "1_1") (pintype "unspecified"))
      (node (ref "H4") (pin "2") (pinfunction "2_2") (pintype "input"))
      (node (ref "Q2") (pin "3") (pinfunction "C_3") (pintype "unspecified"))
      (node (ref "R15") (pin "2") (pinfunction "2_2") (pintype "input"))
      (node (ref "R22") (pin "1") (pinfunction "1_1") (pintype "input"))
      (node (ref "R41") (pin "2") (pinfunction "2_2") (pintype "input"))
      (node (ref "R42") (pin "2") (pinfunction "2_2") (pintype "input"))
      (node (ref "R44") (pin "2") (pinfunction "2_2") (pintype "input"))
      (node (ref "R45") (pin "2") (pinfunction "2_2") (pintype "input"))
      (node (ref "R49") (pin "1") (pinfunction "1_1") (pintype "input"))
      (node (ref "R52") (pin "2") (pinfunction "2_2") (pintype "input"))
      (node (ref "R55") (pin "1") (pinfunction "1_1") (pintype "input"))
      (node (ref "R6") (pin "1") (pinfunction "1_1") (pintype "input"))
      (node (ref "SW1") (pin "1") (pinfunction "1_1") (pintype "input"))
      (node (ref "SW1") (pin "2") (pinfunction "2_2") (pintype "input"))
      (node (ref "SW2") (pin "1") (pinfunction "1_1") (pintype "input"))
      (node (ref "SW2") (pin "2") (pinfunction "2_2") (pintype "input"))
      (node (ref "TP1") (pin "1") (pinfunction "1_1") (pintype "input"))
      (node (ref "TP2") (pin "1") (pinfunction "1_1") (pintype "input"))
      (node (ref "TP3") (pin "1") (pinfunction "1_1") (pintype "input"))
      (node (ref "TP4") (pin "1") (pinfunction "1_1") (pintype "input"))
      (node (ref "U1") (pin "23") (pinfunction "VSS_23") (pintype "input"))
      (node (ref "U1") (pin "47") (pinfunction "VSS_47") (pintype "input"))
      (node (ref "U1") (pin "8") (pinfunction "VSSA_8") (pintype "input"))
      (node (ref "U2") (pin "1") (pinfunction "TEMP_1") (pintype "input"))
      (node (ref "U2") (pin "3") (pinfunction "GND_3") (pintype "input"))
      (node (ref "U3") (pin "1") (pinfunction "VSS_1") (pintype "input"))
      (node (ref "U6") (pin "2") (pinfunction "S_2") (pintype "input"))
      (node (ref "U7") (pin "4") (pinfunction "GND_4") (pintype "input"))
      (node (ref "U8") (pin "4") (pinfunction "GND_4") (pintype "input"))
      (node (ref "U9") (pin "4") (pinfunction "GND_4") (pintype "input"))
      (node (ref "USB1") (pin "1") (pinfunction "GND_1") (pintype "input"))
      (node (ref "USB1") (pin "12") (pinfunction "GND_12") (pintype "input"))
      (node (ref "USB1") (pin "13") (pinfunction "SHELL_13") (pintype "input"))
      (node (ref "USB1") (pin "14") (pinfunction "SHELL_14") (pintype "input"))
      (node (ref "X1") (pin "2") (pinfunction "GND_2") (pintype "input"))
      (node (ref "X1") (pin "4") (pinfunction "GND_4") (pintype "input"))
    )
    (net (code "16") (name "Net-(C2-Pad1)") (class "Default")
      (node (ref "C2") (pin "1") (pinfunction "1_1") (pintype "unspecified"))
      (node (ref "C6") (pin "2") (pinfunction "2_2") (pintype "input"))
      (node (ref "C7") (pin "2") (pinfunction "2_2") (pintype "unspecified"))
      (node (ref "R2") (pin "1") (pinfunction "1_1") (pintype "input"))
    )
    (net (code "17") (name "Net-(C3-Pad1)") (class "Default")
      (node (ref "C3") (pin "1") (pinfunction "1_1") (pintype "unspecified"))
      (node (ref "C8") (pin "2") (pinfunction "2_2") (pintype "unspecified"))
      (node (ref "R2") (pin "2") (pinfunction "2_2") (pintype "input"))
      (node (ref "R3") (pin "1") (pinfunction "1_1") (pintype "input"))
    )
    (net (code "18") (name "Net-(C4-Pad1)") (class "Default")
      (node (ref "C4") (pin "1") (pinfunction "1_1") (pintype "unspecified"))
      (node (ref "C9") (pin "2") (pinfunction "2_2") (pintype "unspecified"))
      (node (ref "R3") (pin "2") (pinfunction "2_2") (pintype "input"))
      (node (ref "R4") (pin "1") (pinfunction "1_1") (pintype "input"))
    )
    (net (code "19") (name "Net-(C10-Pad2)") (class "Default")
      (node (ref "C10") (pin "2") (pinfunction "2_2") (pintype "unspecified"))
      (node (ref "C5") (pin "1") (pinfunction "1_1") (pintype "unspecified"))
      (node (ref "R4") (pin "2") (pinfunction "2_2") (pintype "input"))
      (node (ref "R5") (pin "1") (pinfunction "1_1") (pintype "input"))
    )
    (net (code "20") (name "Net-(C14-Pad1)") (class "Default")
      (node (ref "C14") (pin "1") (pinfunction "1_1") (pintype "unspecified"))
      (node (ref "C40") (pin "1") (pinfunction "1_1") (pintype "input"))
      (node (ref "L1") (pin "2") (pinfunction "2_2") (pintype "input"))
    )
    (net (code "21") (name "Net-(C17-Pad2)") (class "Default")
      (node (ref "C17") (pin "2") (pinfunction "2_2") (pintype "unspecified"))
      (node (ref "C39") (pin "2") (pinfunction "2_2") (pintype "input"))
      (node (ref "R19") (pin "2") (pinfunction "2_2") (pintype "unspecified"))
    )
    (net (code "22") (name "Net-(C23-Pad1)") (class "Default")
      (node (ref "C23") (pin "1") (pinfunction "1_1") (pintype "unspecified"))
      (node (ref "R27") (pin "1") (pinfunction "1_1") (pintype "input"))
    )
    (net (code "23") (name "Net-(C27-Pad1)") (class "Default")
      (node (ref "C27") (pin "1") (pinfunction "1_1") (pintype "unspecified"))
      (node (ref "R46") (pin "1") (pinfunction "1_1") (pintype "unspecified"))
      (node (ref "R48") (pin "2") (pinfunction "2_2") (pintype "unspecified"))
    )
    (net (code "24") (name "Net-(C27-Pad2)") (class "Default")
      (node (ref "C27") (pin "2") (pinfunction "2_2") (pintype "unspecified"))
      (node (ref "H4") (pin "1") (pinfunction "1_1") (pintype "input"))
    )
    (net (code "25") (name "Net-(C32-Pad1)") (class "Default")
      (node (ref "C32") (pin "1") (pinfunction "1_1") (pintype "unspecified"))
      (node (ref "FPC1") (pin "3") (pinfunction "3_3") (pintype "input"))
    )
    (net (code "26") (name "Net-(C32-Pad2)") (class "Default")
      (node (ref "C32") (pin "2") (pinfunction "2_2") (pintype "unspecified"))
      (node (ref "FPC1") (pin "2") (pinfunction "2_2") (pintype "input"))
    )
    (net (code "27") (name "Net-(C33-Pad1)") (class "Default")
      (node (ref "C33") (pin "1") (pinfunction "1_1") (pintype "unspecified"))
      (node (ref "FPC1") (pin "1") (pinfunction "1_1") (pintype "input"))
    )
    (net (code "28") (name "Net-(D1-A)") (class "Default")
      (node (ref "D1") (pin "1") (pinfunction "A_1") (pintype "unspecified"))
      (node (ref "R40") (pin "1") (pinfunction "1_1") (pintype "input"))
    )
    (net (code "29") (name "Net-(D1-K)") (class "Default")
      (node (ref "D1") (pin "2") (pinfunction "K_2") (pintype "unspecified"))
      (node (ref "D2") (pin "1") (pinfunction "A_1") (pintype "unspecified"))
      (node (ref "Q1") (pin "1") (pinfunction "B_1") (pintype "input"))
      (node (ref "Q2") (pin "1") (pinfunction "B_1") (pintype "unspecified"))
      (node (ref "R47") (pin "1") (pinfunction "1_1") (pintype "input"))
    )
    (net (code "30") (name "Net-(D2-K)") (class "Default")
      (node (ref "D2") (pin "2") (pinfunction "K_2") (pintype "unspecified"))
      (node (ref "R49") (pin "2") (pinfunction "2_2") (pintype "input"))
    )
    (net (code "31") (name "Net-(L2-Pad1)") (class "Default")
      (node (ref "L2") (pin "1") (pinfunction "1_1") (pintype "input"))
      (node (ref "L3") (pin "1") (pinfunction "1_1") (pintype "input"))
    )
    (net (code "32") (name "Net-(L2-Pad2)") (class "Default")
      (node (ref "L2") (pin "2") (pinfunction "2_2") (pintype "input"))
      (node (ref "R17") (pin "1") (pinfunction "1_1") (pintype "unspecified"))
    )
    (net (code "33") (name "Net-(L3-Pad2)") (class "Default")
      (node (ref "L3") (pin "2") (pinfunction "2_2") (pintype "input"))
      (node (ref "R16") (pin "1") (pinfunction "1_1") (pintype "unspecified"))
    )
    (net (code "34") (name "Net-(LED11-A)") (class "Default")
      (node (ref "C24") (pin "2") (pinfunction "2_2") (pintype "unspecified"))
      (node (ref "LED11") (pin "1") (pinfunction "A_1") (pintype "input"))
      (node (ref "LED12") (pin "1") (pinfunction "A_1") (pintype "input"))
      (node (ref "U2") (pin "4") (pinfunction "Vcc_4") (pintype "input"))
      (node (ref "U2") (pin "8") (pinfunction "CE_8") (pintype "input"))
      (node (ref "USB1") (pin "11") (pinfunction "VBUS_11") (pintype "input"))
      (node (ref "USB1") (pin "2") (pinfunction "VBUS_2") (pintype "input"))
    )
    (net (code "35") (name "Net-(LED11-K)") (class "Default")
      (node (ref "LED11") (pin "2") (pinfunction "K_2") (pintype "input"))
      (node (ref "R38") (pin "2") (pinfunction "2_2") (pintype "input"))
    )
    (net (code "36") (name "Net-(LED12-K)") (class "Default")
      (node (ref "LED12") (pin "2") (pinfunction "K_2") (pintype "input"))
      (node (ref "R39") (pin "2") (pinfunction "2_2") (pintype "input"))
    )
    (net (code "37") (name "Net-(Q1-E)") (class "Default")
      (node (ref "Q1") (pin "2") (pinfunction "E_2") (pintype "input"))
      (node (ref "R46") (pin "2") (pinfunction "2_2") (pintype "unspecified"))
    )
    (net (code "38") (name "Net-(Q2-E)") (class "Default")
      (node (ref "Q2") (pin "2") (pinfunction "E_2") (pintype "unspecified"))
      (node (ref "R48") (pin "1") (pinfunction "1_1") (pintype "unspecified"))
    )
    (net (code "39") (name "Net-(R13-Pad1)") (class "Default")
      (node (ref "R13") (pin "1") (pinfunction "1_1") (pintype "input"))
      (node (ref "SW1") (pin "3") (pinfunction "3_3") (pintype "input"))
      (node (ref "SW1") (pin "4") (pinfunction "4_4") (pintype "input"))
    )
    (net (code "40") (name "Net-(R14-Pad1)") (class "Default")
      (node (ref "R14") (pin "1") (pinfunction "1_1") (pintype "input"))
      (node (ref "SW2") (pin "3") (pinfunction "3_3") (pintype "input"))
      (node (ref "SW2") (pin "4") (pinfunction "4_4") (pintype "input"))
    )
    (net (code "41") (name "Net-(R42-Pad1)") (class "Default")
      (node (ref "R42") (pin "1") (pinfunction "1_1") (pintype "input"))
      (node (ref "R43") (pin "2") (pinfunction "2_2") (pintype "input"))
      (node (ref "R45") (pin "1") (pinfunction "1_1") (pintype "input"))
    )
    (net (code "42") (name "Net-(U1-BOOT0)") (class "Default")
      (node (ref "R15") (pin "1") (pinfunction "1_1") (pintype "input"))
      (node (ref "U1") (pin "44") (pinfunction "BOOT0_44") (pintype "input"))
    )
    (net (code "43") (name "Net-(U1-PB6)") (class "Default")
      (node (ref "R14") (pin "2") (pinfunction "2_2") (pintype "input"))
      (node (ref "U1") (pin "42") (pinfunction "PB6_42") (pintype "input"))
    )
    (net (code "44") (name "Net-(U1-PB7)") (class "Default")
      (node (ref "R13") (pin "2") (pinfunction "2_2") (pintype "input"))
      (node (ref "U1") (pin "43") (pinfunction "PB7_43") (pintype "input"))
    )
    (net (code "45") (name "Net-(U1-PF0-OSC_IN)") (class "Default")
      (node (ref "C12") (pin "2") (pinfunction "2_2") (pintype "input"))
      (node (ref "U1") (pin "5") (pinfunction "PF0-OSC_IN_5") (pintype "input"))
      (node (ref "X1") (pin "3") (pinfunction "3_3") (pintype "input"))
    )
    (net (code "46") (name "Net-(U1-PF1-OSC_OUT)") (class "Default")
      (node (ref "C16") (pin "2") (pinfunction "2_2") (pintype "input"))
      (node (ref "U1") (pin "6") (pinfunction "PF1-OSC_OUT_6") (pintype "input"))
      (node (ref "X1") (pin "1") (pinfunction "1_1") (pintype "input"))
    )
    (net (code "47") (name "Net-(U2-CHRG#)") (class "Default")
      (node (ref "R38") (pin "1") (pinfunction "1_1") (pintype "input"))
      (node (ref "U2") (pin "7") (pinfunction "CHRG#_7") (pintype "input"))
    )
    (net (code "48") (name "Net-(U2-PROG)") (class "Default")
      (node (ref "R43") (pin "1") (pinfunction "1_1") (pintype "input"))
      (node (ref "U2") (pin "2") (pinfunction "PROG_2") (pintype "input"))
    )
    (net (code "49") (name "Net-(U2-STDBY#)") (class "Default")
      (node (ref "R39") (pin "1") (pinfunction "1_1") (pintype "input"))
      (node (ref "U2") (pin "6") (pinfunction "STDBY#_6") (pintype "input"))
    )
    (net (code "50") (name "Net-(U4-CS)") (class "Default")
      (node (ref "R55") (pin "2") (pinfunction "2_2") (pintype "input"))
      (node (ref "U4") (pin "2") (pinfunction "CS_2") (pintype "input"))
    )
    (net (code "51") (name "Net-(U4-OC)") (class "Default")
      (node (ref "U4") (pin "3") (pinfunction "OC_3") (pintype "input"))
      (node (ref "U6") (pin "1") (pinfunction "G_1") (pintype "input"))
    )
    (net (code "52") (name "Net-(U4-OD)") (class "Default")
      (node (ref "U4") (pin "1") (pinfunction "OD_1") (pintype "input"))
      (node (ref "U5") (pin "1") (pinfunction "G_1") (pintype "input"))
    )
    (net (code "53") (name "Net-(U4-VCC)") (class "Default")
      (node (ref "C31") (pin "2") (pinfunction "2_2") (pintype "unspecified"))
      (node (ref "R50") (pin "1") (pinfunction "1_1") (pintype "input"))
      (node (ref "U4") (pin "5") (pinfunction "VCC_5") (pintype "input"))
    )
    (net (code "54") (name "Net-(U5-D)") (class "Default")
      (node (ref "U5") (pin "3") (pinfunction "D_3") (pintype "input"))
      (node (ref "U6") (pin "3") (pinfunction "D_3") (pintype "input"))
    )
    (net (code "55") (name "Net-(U7A-IN1+)") (class "Default")
      (node (ref "C18") (pin "2") (pinfunction "2_2") (pintype "input"))
      (node (ref "R16") (pin "2") (pinfunction "2_2") (pintype "unspecified"))
      (node (ref "R20") (pin "2") (pinfunction "2_2") (pintype "input"))
      (node (ref "U7") (pin "3") (pinfunction "IN1+_3") (pintype "input"))
    )
    (net (code "56") (name "Net-(U7A-IN1-)") (class "Default")
      (node (ref "R18") (pin "1") (pinfunction "1_1") (pintype "input"))
      (node (ref "U7") (pin "1") (pinfunction "OUT_1") (pintype "output"))
      (node (ref "U7") (pin "2") (pinfunction "IN1-_2") (pintype "input"))
    )
    (net (code "57") (name "Net-(U7B-IN2+)") (class "Default")
      (node (ref "C18") (pin "1") (pinfunction "1_1") (pintype "input"))
      (node (ref "R17") (pin "2") (pinfunction "2_2") (pintype "unspecified"))
      (node (ref "R23") (pin "1") (pinfunction "1_1") (pintype "input"))
      (node (ref "U7") (pin "5") (pinfunction "IN2+_5") (pintype "input"))
    )
    (net (code "58") (name "Net-(U7B-IN2-)") (class "Default")
      (node (ref "R24") (pin "1") (pinfunction "1_1") (pintype "input"))
      (node (ref "U7") (pin "6") (pinfunction "IN2-_6") (pintype "input"))
      (node (ref "U7") (pin "7") (pinfunction "OUT2_7") (pintype "output"))
    )
    (net (code "59") (name "Net-(U8A-IN1+)") (class "Default")
      (node (ref "C39") (pin "1") (pinfunction "1_1") (pintype "input"))
      (node (ref "R18") (pin "2") (pinfunction "2_2") (pintype "input"))
      (node (ref "R19") (pin "1") (pinfunction "1_1") (pintype "unspecified"))
      (node (ref "U8") (pin "3") (pinfunction "IN1+_3") (pintype "input"))
    )
    (net (code "60") (name "Net-(U8A-IN1-)") (class "Default")
      (node (ref "C38") (pin "1") (pinfunction "1_1") (pintype "input"))
      (node (ref "R24") (pin "2") (pinfunction "2_2") (pintype "input"))
      (node (ref "R26") (pin "1") (pinfunction "1_1") (pintype "unspecified"))
      (node (ref "U8") (pin "2") (pinfunction "IN1-_2") (pintype "input"))
    )
    (net (code "61") (name "Net-(U8A-OUT)") (class "Default")
      (node (ref "C20") (pin "2") (pinfunction "2_2") (pintype "input"))
      (node (ref "C38") (pin "2") (pinfunction "2_2") (pintype "input"))
      (node (ref "R26") (pin "2") (pinfunction "2_2") (pintype "unspecified"))
      (node (ref "U8") (pin "1") (pinfunction "OUT_1") (pintype "output"))
    )
    (net (code "62") (name "Net-(U8B-IN2+)") (class "Default")
      (node (ref "C20") (pin "1") (pinfunction "1_1") (pintype "input"))
      (node (ref "R21") (pin "1") (pinfunction "1_1") (pintype "input"))
      (node (ref "R22") (pin "2") (pinfunction "2_2") (pintype "input"))
      (node (ref "U8") (pin "5") (pinfunction "IN2+_5") (pintype "input"))
    )
    (net (code "63") (name "Net-(U8B-IN2-)") (class "Default")
      (node (ref "C37") (pin "2") (pinfunction "2_2") (pintype "unspecified"))
      (node (ref "R25") (pin "1") (pinfunction "1_1") (pintype "input"))
      (node (ref "R27") (pin "2") (pinfunction "2_2") (pintype "input"))
      (node (ref "U8") (pin "6") (pinfunction "IN2-_6") (pintype "input"))
    )
    (net (code "64") (name "Net-(U9A-IN1+)") (class "Default")
      (node (ref "C6") (pin "1") (pinfunction "1_1") (pintype "input"))
      (node (ref "R1") (pin "1") (pinfunction "1_1") (pintype "input"))
      (node (ref "R6") (pin "2") (pinfunction "2_2") (pintype "input"))
      (node (ref "U9") (pin "3") (pinfunction "IN1+_3") (pintype "input"))
    )
    (net (code "65") (name "Net-(U9A-IN1-)") (class "Default")
      (node (ref "R10") (pin "2") (pinfunction "2_2") (pintype "input"))
      (node (ref "R7") (pin "2") (pinfunction "2_2") (pintype "unspecified"))
      (node (ref "U9") (pin "2") (pinfunction "IN1-_2") (pintype "input"))
    )
    (net (code "66") (name "Net-(U9A-OUT)") (class "Default")
      (node (ref "C40") (pin "2") (pinfunction "2_2") (pintype "input"))
      (node (ref "R7") (pin "1") (pinfunction "1_1") (pintype "unspecified"))
      (node (ref "R9") (pin "1") (pinfunction "1_1") (pintype "unspecified"))
      (node (ref "U9") (pin "1") (pinfunction "OUT_1") (pintype "output"))
    )
    (net (code "67") (name "Net-(U9B-IN2+)") (class "Default")
      (node (ref "C11") (pin "1") (pinfunction "1_1") (pintype "unspecified"))
      (node (ref "R10") (pin "1") (pinfunction "1_1") (pintype "input"))
      (node (ref "U9") (pin "5") (pinfunction "IN2+_5") (pintype "input"))
    )
    (net (code "68") (name "Net-(U9B-IN2-)") (class "Default")
      (node (ref "R12") (pin "1") (pinfunction "1_1") (pintype "unspecified"))
      (node (ref "R9") (pin "2") (pinfunction "2_2") (pintype "unspecified"))
      (node (ref "U9") (pin "6") (pinfunction "IN2-_6") (pintype "input"))
    )
    (net (code "69") (name "Net-(U9B-OUT2)") (class "Default")
      (node (ref "C14") (pin "2") (pinfunction "2_2") (pintype "unspecified"))
      (node (ref "L1") (pin "1") (pinfunction "1_1") (pintype "input"))
      (node (ref "R12") (pin "2") (pinfunction "2_2") (pintype "unspecified"))
      (node (ref "U9") (pin "7") (pinfunction "OUT2_7") (pintype "output"))
    )
    (net (code "70") (name "Net-(USB1-CC1)") (class "Default")
      (node (ref "R44") (pin "1") (pinfunction "1_1") (pintype "input"))
      (node (ref "USB1") (pin "4") (pinfunction "CC1_4") (pintype "input"))
    )
    (net (code "71") (name "Net-(USB1-CC2)") (class "Default")
      (node (ref "R41") (pin "1") (pinfunction "1_1") (pintype "input"))
      (node (ref "USB1") (pin "10") (pinfunction "CC2_10") (pintype "input"))
    )
    (net (code "72") (name "VCC") (class "Default")
      (node (ref "C25") (pin "1") (pinfunction "1_1") (pintype "unspecified"))
      (node (ref "C29") (pin "2") (pinfunction "2_2") (pintype "unspecified"))
      (node (ref "Q1") (pin "3") (pinfunction "C_3") (pintype "input"))
      (node (ref "R40") (pin "2") (pinfunction "2_2") (pintype "input"))
      (node (ref "SW3") (pin "2") (pinfunction "2_2") (pintype "input"))
      (node (ref "SW3") (pin "3") (pinfunction "3_3") (pintype "input"))
      (node (ref "U3") (pin "3") (pinfunction "VIN_3") (pintype "input"))
    )
    (net (code "73") (name "unconnected-(U1-NRST-Pad7)") (class "Default")
      (node (ref "U1") (pin "7") (pinfunction "NRST_7") (pintype "input"))
    )
    (net (code "74") (name "unconnected-(U1-PA1-Pad11)") (class "Default")
      (node (ref "U1") (pin "11") (pinfunction "PA1_11") (pintype "input"))
    )
    (net (code "75") (name "unconnected-(U1-PA2-Pad12)") (class "Default")
      (node (ref "U1") (pin "12") (pinfunction "PA2_12") (pintype "input"))
    )
    (net (code "76") (name "unconnected-(U1-PA3-Pad13)") (class "Default")
      (node (ref "U1") (pin "13") (pinfunction "PA3_13") (pintype "input"))
    )
    (net (code "77") (name "unconnected-(U1-PA4-Pad14)") (class "Default")
      (node (ref "U1") (pin "14") (pinfunction "PA4_14") (pintype "input"))
    )
    (net (code "78") (name "unconnected-(U1-PA5-Pad15)") (class "Default")
      (node (ref "U1") (pin "15") (pinfunction "PA5_15") (pintype "input"))
    )
    (net (code "79") (name "unconnected-(U1-PA6-Pad16)") (class "Default")
      (node (ref "U1") (pin "16") (pinfunction "PA6_16") (pintype "input"))
    )
    (net (code "80") (name "unconnected-(U1-PA7-Pad17)") (class "Default")
      (node (ref "U1") (pin "17") (pinfunction "PA7_17") (pintype "input"))
    )
    (net (code "81") (name "unconnected-(U1-PA8-Pad29)") (class "Default")
      (node (ref "U1") (pin "29") (pinfunction "PA8_29") (pintype "input"))
    )
    (net (code "82") (name "unconnected-(U1-PA10-Pad31)") (class "Default")
      (node (ref "U1") (pin "31") (pinfunction "PA10_31") (pintype "input"))
    )
    (net (code "83") (name "unconnected-(U1-PA11-Pad32)") (class "Default")
      (node (ref "U1") (pin "32") (pinfunction "PA11_32") (pintype "input"))
    )
    (net (code "84") (name "unconnected-(U1-PA12-Pad33)") (class "Default")
      (node (ref "U1") (pin "33") (pinfunction "PA12_33") (pintype "input"))
    )
    (net (code "85") (name "unconnected-(U1-PB0-Pad18)") (class "Default")
      (node (ref "U1") (pin "18") (pinfunction "PB0_18") (pintype "input"))
    )
    (net (code "86") (name "unconnected-(U1-PB1-Pad19)") (class "Default")
      (node (ref "U1") (pin "19") (pinfunction "PB1_19") (pintype "input"))
    )
    (net (code "87") (name "unconnected-(U1-PB2-Pad20)") (class "Default")
      (node (ref "U1") (pin "20") (pinfunction "PB2_20") (pintype "input"))
    )
    (net (code "88") (name "unconnected-(U1-PB8-Pad45)") (class "Default")
      (node (ref "U1") (pin "45") (pinfunction "PB8_45") (pintype "input"))
    )
    (net (code "89") (name "unconnected-(U1-PB9-Pad46)") (class "Default")
      (node (ref "U1") (pin "46") (pinfunction "PB9_46") (pintype "input"))
    )
    (net (code "90") (name "unconnected-(U1-PB10-Pad21)") (class "Default")
      (node (ref "U1") (pin "21") (pinfunction "PB10_21") (pintype "input"))
    )
    (net (code "91") (name "unconnected-(U1-PB11-Pad22)") (class "Default")
      (node (ref "U1") (pin "22") (pinfunction "PB11_22") (pintype "input"))
    )
    (net (code "92") (name "unconnected-(U1-PB12-Pad25)") (class "Default")
      (node (ref "U1") (pin "25") (pinfunction "PB12_25") (pintype "input"))
    )
    (net (code "93") (name "unconnected-(U1-PB13-Pad26)") (class "Default")
      (node (ref "U1") (pin "26") (pinfunction "PB13_26") (pintype "input"))
    )
    (net (code "94") (name "unconnected-(U1-PB14-Pad27)") (class "Default")
      (node (ref "U1") (pin "27") (pinfunction "PB14_27") (pintype "input"))
    )
    (net (code "95") (name "unconnected-(U1-PC13-Pad2)") (class "Default")
      (node (ref "U1") (pin "2") (pinfunction "PC13_2") (pintype "input"))
    )
    (net (code "96") (name "unconnected-(U1-PC14-OSC32_IN-Pad3)") (class "Default")
      (node (ref "U1") (pin "3") (pinfunction "PC14-OSC32_IN_3") (pintype "input"))
    )
    (net (code "97") (name "unconnected-(U1-PC15-OSC32_OUT-Pad4)") (class "Default")
      (node (ref "U1") (pin "4") (pinfunction "PC15-OSC32_OUT_4") (pintype "input"))
    )
    (net (code "98") (name "unconnected-(U1-PF6-Pad35)") (class "Default")
      (node (ref "U1") (pin "35") (pinfunction "PF6_35") (pintype "input"))
    )
    (net (code "99") (name "unconnected-(U1-PF7-Pad36)") (class "Default")
      (node (ref "U1") (pin "36") (pinfunction "PF7_36") (pintype "input"))
    )
    (net (code "100") (name "unconnected-(U4-TD-Pad4)") (class "Default")
      (node (ref "U4") (pin "4") (pinfunction "TD_4") (pintype "input"))
    )
    (net (code "101") (name "unconnected-(USB1-DN1-Pad7)") (class "Default")
      (node (ref "USB1") (pin "7") (pinfunction "DN1_7") (pintype "input"))
    )
    (net (code "102") (name "unconnected-(USB1-DN2-Pad5)") (class "Default")
      (node (ref "USB1") (pin "5") (pinfunction "DN2_5") (pintype "input"))
    )
    (net (code "103") (name "unconnected-(USB1-DP1-Pad6)") (class "Default")
      (node (ref "USB1") (pin "6") (pinfunction "DP1_6") (pintype "input"))
    )
    (net (code "104") (name "unconnected-(USB1-DP2-Pad8)") (class "Default")
      (node (ref "USB1") (pin "8") (pinfunction "DP2_8") (pintype "input"))
    )
    (net (code "105") (name "unconnected-(USB1-SBU1-Pad9)") (class "Default")
      (node (ref "USB1") (pin "9") (pinfunction "SBU1_9") (pintype "input"))
    )
    (net (code "106") (name "unconnected-(USB1-SBU2-Pad3)") (class "Default")
      (node (ref "USB1") (pin "3") (pinfunction "SBU2_3") (pintype "input"))
    )
  )
)
